# Relay_ORWH-SH-105D1F.net
KiCad netlist of a schematic drawn in Altium Designer
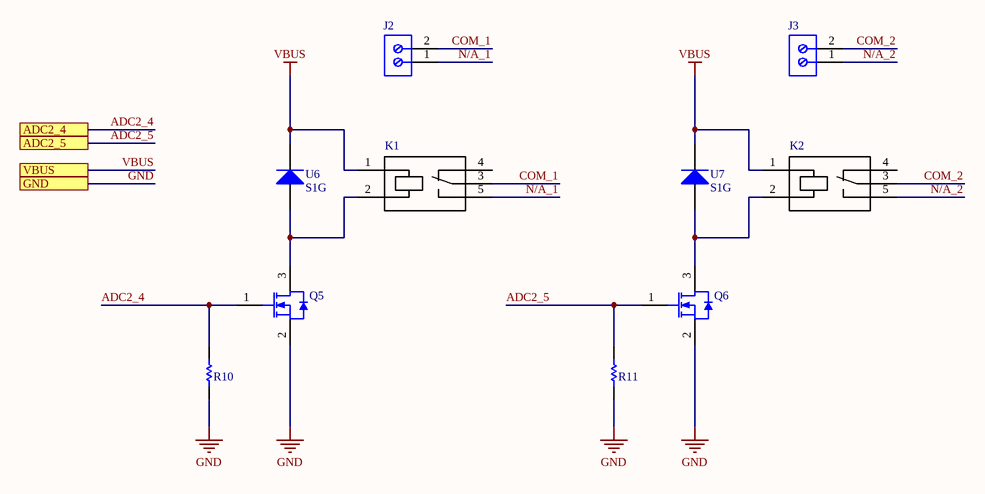
[diagram p0: Relay_ORWH-SH-105D1F.SchDoc]

(export (version "E")
  (design (tool "Eeschema 10.0.6"))
  (components
    (comp (ref "J2")
      (value "691709710302")
      (footprint "691709710302")
      (description "Serie 7097 - 5.00 mm Horizontal Entry SMT with Pressure Clamp WR-TBL, 2 pin")
      (fields (field (name "MANUFACTURER") "Wurth Elektronik") (field (name "PUBLISHER") "WurthElektronik"))
      (libsource (lib "Altium Content Vault") (part "WE-CN-1P-F-TB2"))
    )
    (comp (ref "J3")
      (value "691709710302")
      (footprint "691709710302")
      (description "Serie 7097 - 5.00 mm Horizontal Entry SMT with Pressure Clamp WR-TBL, 2 pin")
      (fields (field (name "MANUFACTURER") "Wurth Elektronik") (field (name "PUBLISHER") "WurthElektronik"))
      (libsource (lib "Altium Content Vault") (part "WE-CN-1P-F-TB2"))
    )
    (comp (ref "K1")
      (value "ORWH-SH-105D1F,000")
      (footprint "TE_ORWH-SH-105D1F,000")
      (description "Electromechanical Relay 5VDC 15A SPDT __ 19.2mm 15.5mm 15mm__ THT General Purpose Relay")
      (fields (field (name "DIGI-KEY_PART_NUMBER") "PB2032-ND") (field (name "MF") "TE Connectivity"))
      (libsource (lib "LIB_FIT") (part "ORWH-SH-105D1F,000"))
    )
    (comp (ref "K2")
      (value "ORWH-SH-105D1F,000")
      (footprint "TE_ORWH-SH-105D1F,000")
      (description "Electromechanical Relay 5VDC 15A SPDT __ 19.2mm 15.5mm 15mm__ THT General Purpose Relay")
      (fields (field (name "DIGI-KEY_PART_NUMBER") "PB2032-ND") (field (name "MF") "TE Connectivity"))
      (libsource (lib "LIB_FIT") (part "ORWH-SH-105D1F,000"))
    )
    (comp (ref "Q5")
      (value "BSS138-7-F")
      (footprint "DIOD-SOT23-3_V")
      (description "N-Channel Enhancement Mode Mosfet, 50 V, 0.2 A, -55 to 150 degC, 3-Pin SOT23, RoHS, Tape and Reel")
      (fields (field (name "MANUFACTURER") "Diodes Inc"))
      (libsource (lib "Altium Content Vault") (part "NEMOS-GSD-3"))
    )
    (comp (ref "Q6")
      (value "BSS138-7-F")
      (footprint "DIOD-SOT23-3_V")
      (description "N-Channel Enhancement Mode Mosfet, 50 V, 0.2 A, -55 to 150 degC, 3-Pin SOT23, RoHS, Tape and Reel")
      (fields (field (name "MANUFACTURER") "Diodes Inc"))
      (libsource (lib "Altium Content Vault") (part "NEMOS-GSD-3"))
    )
    (comp (ref "R10")
      (value "RK73B2ATTD103J")
      (footprint "RESC2013X60X30NL20T20")
      (fields (field (name "MANUFACTURER") "KOA Speer"))
      (libsource (lib "Altium Content Vault") (part "RES"))
    )
    (comp (ref "R11")
      (value "RK73B2ATTD103J")
      (footprint "RESC2013X60X30NL20T20")
      (fields (field (name "MANUFACTURER") "KOA Speer"))
      (libsource (lib "Altium Content Vault") (part "RES"))
    )
    (comp (ref "U6")
      (value "S1G")
      (footprint "FAIR-DO-214AC-2_V")
      (description "General Purpose Rectifier, 1.4 W, -55 to 150 degC, 2-Pin DO-214AC, RoHS, Tape and Reel")
      (fields (field (name "MANUFACTURER") "Fairchild Semiconductor"))
      (libsource (lib "Altium Content Vault") (part "FAIR-S1G-2"))
    )
    (comp (ref "U7")
      (value "S1G")
      (footprint "FAIR-DO-214AC-2_V")
      (description "General Purpose Rectifier, 1.4 W, -55 to 150 degC, 2-Pin DO-214AC, RoHS, Tape and Reel")
      (fields (field (name "MANUFACTURER") "Fairchild Semiconductor"))
      (libsource (lib "Altium Content Vault") (part "FAIR-S1G-2"))
    )
  )
  (nets
    (net (code "1") (name "/ADC2_4") (class "Default")
      (node (ref "Q5") (pin "1") (pinfunction "G_1") (pintype "passive"))
      (node (ref "R10") (pin "1") (pinfunction "1_1") (pintype "passive"))
    )
    (net (code "2") (name "/ADC2_5") (class "Default")
      (node (ref "Q6") (pin "1") (pinfunction "G_1") (pintype "passive"))
      (node (ref "R11") (pin "1") (pinfunction "1_1") (pintype "passive"))
    )
    (net (code "3") (name "/COM_1") (class "Default")
      (node (ref "J2") (pin "2") (pinfunction "2_2") (pintype "passive"))
      (node (ref "K1") (pin "3") (pinfunction "C_3") (pintype "passive"))
    )
    (net (code "4") (name "/COM_2") (class "Default")
      (node (ref "J3") (pin "2") (pinfunction "2_2") (pintype "passive"))
      (node (ref "K2") (pin "3") (pinfunction "C_3") (pintype "passive"))
    )
    (net (code "5") (name "/N{slash}A_1") (class "Default")
      (node (ref "J2") (pin "1") (pinfunction "1_1") (pintype "passive"))
      (node (ref "K1") (pin "5") (pinfunction "NO_5") (pintype "passive"))
    )
    (net (code "6") (name "/N{slash}A_2") (class "Default")
      (node (ref "J3") (pin "1") (pinfunction "1_1") (pintype "passive"))
      (node (ref "K2") (pin "5") (pinfunction "NO_5") (pintype "passive"))
    )
    (net (code "7") (name "GND") (class "Default")
      (node (ref "Q5") (pin "2") (pinfunction "S_2") (pintype "passive"))
      (node (ref "Q6") (pin "2") (pinfunction "S_2") (pintype "passive"))
      (node (ref "R10") (pin "2") (pinfunction "2_2") (pintype "passive"))
      (node (ref "R11") (pin "2") (pinfunction "2_2") (pintype "passive"))
    )
    (net (code "8") (name "Net-(K1-C2)") (class "Default")
      (node (ref "K1") (pin "2") (pinfunction "C2_2") (pintype "passive"))
      (node (ref "Q5") (pin "3") (pinfunction "D_3") (pintype "passive"))
      (node (ref "U6") (pin "1") (pinfunction "A_1") (pintype "passive"))
    )
    (net (code "9") (name "Net-(K2-C2)") (class "Default")
      (node (ref "K2") (pin "2") (pinfunction "C2_2") (pintype "passive"))
      (node (ref "Q6") (pin "3") (pinfunction "D_3") (pintype "passive"))
      (node (ref "U7") (pin "1") (pinfunction "A_1") (pintype "passive"))
    )
    (net (code "10") (name "VBUS") (class "Default")
      (node (ref "K1") (pin "1") (pinfunction "C1_1") (pintype "passive"))
      (node (ref "K2") (pin "1") (pinfunction "C1_1") (pintype "passive"))
      (node (ref "U6") (pin "2") (pinfunction "K_2") (pintype "passive"))
      (node (ref "U7") (pin "2") (pinfunction "K_2") (pintype "passive"))
    )
    (net (code "11") (name "unconnected-(K1-NC-Pad4)") (class "Default")
      (node (ref "K1") (pin "4") (pinfunction "NC_4") (pintype "passive"))
    )
    (net (code "12") (name "unconnected-(K2-NC-Pad4)") (class "Default")
      (node (ref "K2") (pin "4") (pinfunction "NC_4") (pintype "passive"))
    )
  )
)
